# motor_side.net
KiCad netlist of a schematic drawn in EAGLE
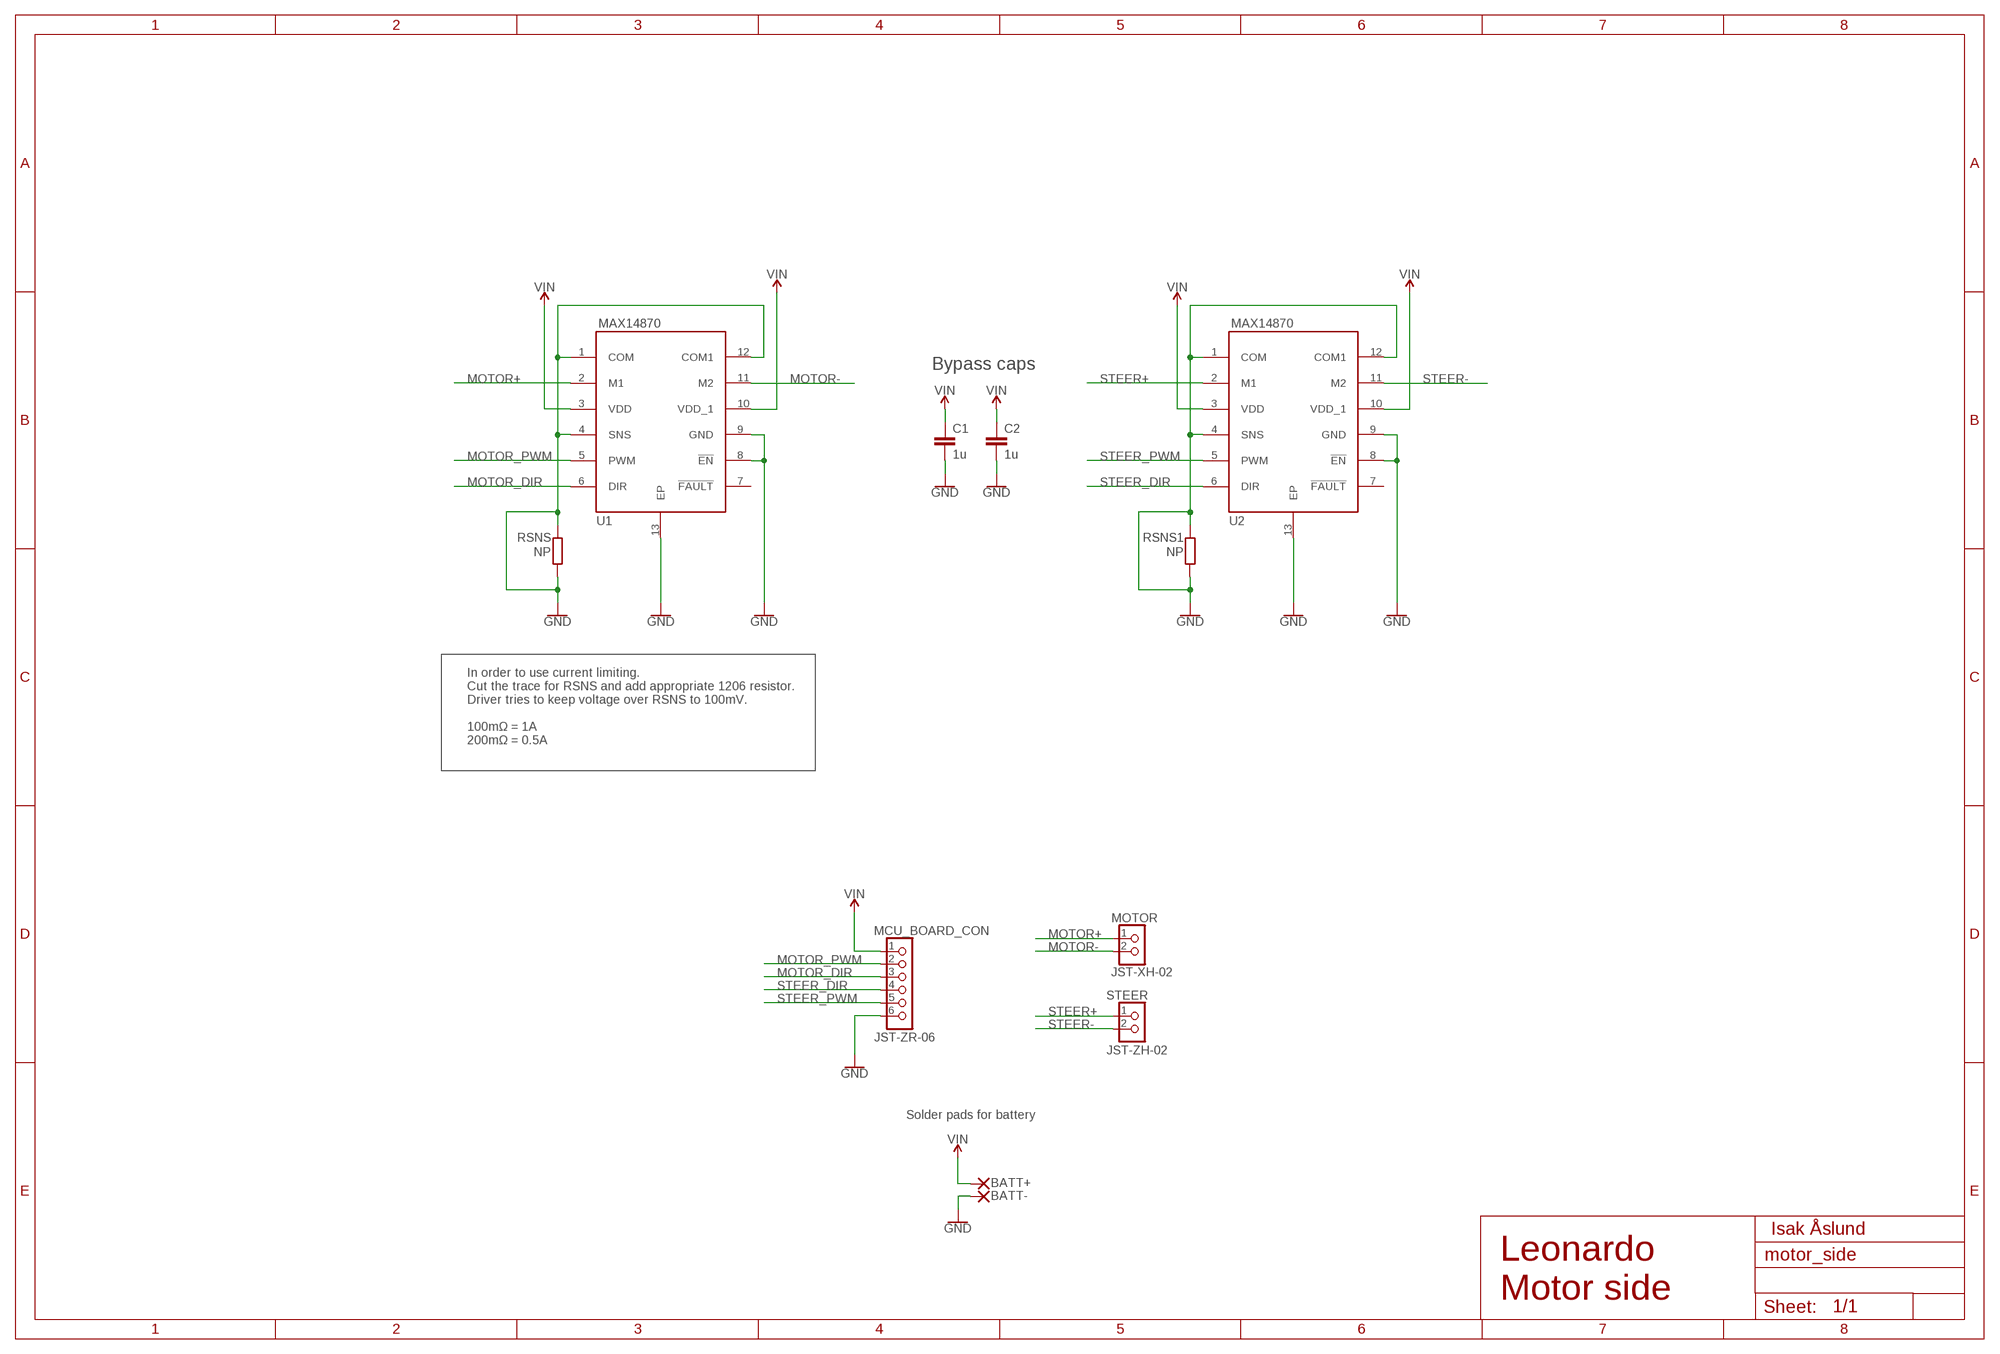
[diagram p0: schematic, sheet 1]

(export (version "E")
  (design (tool "Eeschema 10.0.6"))
  (components
    (comp (ref "BATT+")
      (value "SMD2")
      (footprint "eagle-import:SMD1,27-2,54")
      (libsource (lib "eagle-import") (part "SMD2"))
    )
    (comp (ref "BATT-")
      (value "SMD2")
      (footprint "eagle-import:SMD1,27-2,54")
      (libsource (lib "eagle-import") (part "SMD2"))
    )
    (comp (ref "C1")
      (value "1u")
      (footprint "eagle-import:C0603")
      (libsource (lib "eagle-import") (part "C0603"))
    )
    (comp (ref "C2")
      (value "1u")
      (footprint "eagle-import:C0603")
      (libsource (lib "eagle-import") (part "C0603"))
    )
    (comp (ref "MCU_BOARD_CON")
      (value "JST-ZR-06")
      (footprint "eagle-import:B6B-ZR")
      (libsource (lib "eagle-import") (part "ZR_B6B-ZR"))
    )
    (comp (ref "MOTOR")
      (value "JST-XH-02")
      (footprint "eagle-import:JST-XH-02")
      (libsource (lib "eagle-import") (part "XH-02"))
    )
    (comp (ref "RSNS")
      (value "NP")
      (footprint "eagle-import:R1206")
      (libsource (lib "eagle-import") (part "R1206"))
    )
    (comp (ref "RSNS1")
      (value "NP")
      (footprint "eagle-import:R1206")
      (libsource (lib "eagle-import") (part "R1206"))
    )
    (comp (ref "STEER")
      (value "JST-ZH-02")
      (footprint "eagle-import:B2B-ZR")
      (libsource (lib "eagle-import") (part "ZR_B2B-ZR"))
    )
    (comp (ref "U1")
      (value "MAX14870")
      (footprint "eagle-import:12_TDFN_EP")
      (libsource (lib "eagle-import") (part "MAX14870"))
    )
    (comp (ref "U2")
      (value "MAX14870")
      (footprint "eagle-import:12_TDFN_EP")
      (libsource (lib "eagle-import") (part "MAX14870"))
    )
  )
  (nets
    (net (code "1") (name "/MOTOR+") (class "Default")
      (node (ref "MOTOR") (pin "1") (pinfunction "1_1") (pintype "bidirectional"))
      (node (ref "U1") (pin "2") (pinfunction "M1_2") (pintype "bidirectional"))
    )
    (net (code "2") (name "/MOTOR-") (class "Default")
      (node (ref "MOTOR") (pin "2") (pinfunction "2_2") (pintype "bidirectional"))
      (node (ref "U1") (pin "11") (pinfunction "M2_11") (pintype "bidirectional"))
    )
    (net (code "3") (name "/MOTOR_DIR") (class "Default")
      (node (ref "MCU_BOARD_CON") (pin "3") (pinfunction "3_3") (pintype "passive"))
      (node (ref "U1") (pin "6") (pinfunction "DIR_6") (pintype "bidirectional"))
    )
    (net (code "4") (name "/MOTOR_PWM") (class "Default")
      (node (ref "MCU_BOARD_CON") (pin "2") (pinfunction "2_2") (pintype "passive"))
      (node (ref "U1") (pin "5") (pinfunction "PWM_5") (pintype "bidirectional"))
    )
    (net (code "5") (name "/STEER+") (class "Default")
      (node (ref "STEER") (pin "1") (pinfunction "1_1") (pintype "passive"))
      (node (ref "U2") (pin "2") (pinfunction "M1_2") (pintype "bidirectional"))
    )
    (net (code "6") (name "/STEER-") (class "Default")
      (node (ref "STEER") (pin "2") (pinfunction "2_2") (pintype "passive"))
      (node (ref "U2") (pin "11") (pinfunction "M2_11") (pintype "bidirectional"))
    )
    (net (code "7") (name "/STEER_DIR") (class "Default")
      (node (ref "MCU_BOARD_CON") (pin "4") (pinfunction "4_4") (pintype "passive"))
      (node (ref "U2") (pin "6") (pinfunction "DIR_6") (pintype "bidirectional"))
    )
    (net (code "8") (name "/STEER_PWM") (class "Default")
      (node (ref "MCU_BOARD_CON") (pin "5") (pinfunction "5_5") (pintype "passive"))
      (node (ref "U2") (pin "5") (pinfunction "PWM_5") (pintype "bidirectional"))
    )
    (net (code "9") (name "GND") (class "Default")
      (node (ref "BATT-") (pin "1") (pinfunction "P_1") (pintype "passive"))
      (node (ref "C1") (pin "2") (pinfunction "2_2") (pintype "passive"))
      (node (ref "C2") (pin "2") (pinfunction "2_2") (pintype "passive"))
      (node (ref "MCU_BOARD_CON") (pin "6") (pinfunction "6_6") (pintype "passive"))
      (node (ref "RSNS") (pin "1") (pinfunction "1_1") (pintype "passive"))
      (node (ref "RSNS") (pin "2") (pinfunction "2_2") (pintype "passive"))
      (node (ref "RSNS1") (pin "1") (pinfunction "1_1") (pintype "passive"))
      (node (ref "RSNS1") (pin "2") (pinfunction "2_2") (pintype "passive"))
      (node (ref "U1") (pin "1") (pinfunction "COM_1") (pintype "bidirectional"))
      (node (ref "U1") (pin "12") (pinfunction "COM1_12") (pintype "bidirectional"))
      (node (ref "U1") (pin "13") (pinfunction "EP_13") (pintype "bidirectional"))
      (node (ref "U1") (pin "4") (pinfunction "SNS_4") (pintype "bidirectional"))
      (node (ref "U1") (pin "8") (pinfunction "~{EN}_8") (pintype "bidirectional"))
      (node (ref "U1") (pin "9") (pinfunction "GND_9") (pintype "bidirectional"))
      (node (ref "U2") (pin "1") (pinfunction "COM_1") (pintype "bidirectional"))
      (node (ref "U2") (pin "12") (pinfunction "COM1_12") (pintype "bidirectional"))
      (node (ref "U2") (pin "13") (pinfunction "EP_13") (pintype "bidirectional"))
      (node (ref "U2") (pin "4") (pinfunction "SNS_4") (pintype "bidirectional"))
      (node (ref "U2") (pin "8") (pinfunction "~{EN}_8") (pintype "bidirectional"))
      (node (ref "U2") (pin "9") (pinfunction "GND_9") (pintype "bidirectional"))
    )
    (net (code "10") (name "VIN") (class "Default")
      (node (ref "BATT+") (pin "1") (pinfunction "P_1") (pintype "passive"))
      (node (ref "C1") (pin "1") (pinfunction "1_1") (pintype "passive"))
      (node (ref "C2") (pin "1") (pinfunction "1_1") (pintype "passive"))
      (node (ref "MCU_BOARD_CON") (pin "1") (pinfunction "1_1") (pintype "passive"))
      (node (ref "U1") (pin "10") (pinfunction "VDD_1_10") (pintype "bidirectional"))
      (node (ref "U1") (pin "3") (pinfunction "VDD_3") (pintype "bidirectional"))
      (node (ref "U2") (pin "10") (pinfunction "VDD_1_10") (pintype "bidirectional"))
      (node (ref "U2") (pin "3") (pinfunction "VDD_3") (pintype "bidirectional"))
    )
    (net (code "11") (name "unconnected-(U1-~{FAULT}-Pad7)") (class "Default")
      (node (ref "U1") (pin "7") (pinfunction "~{FAULT}_7") (pintype "bidirectional"))
    )
    (net (code "12") (name "unconnected-(U2-~{FAULT}-Pad7)") (class "Default")
      (node (ref "U2") (pin "7") (pinfunction "~{FAULT}_7") (pintype "bidirectional"))
    )
  )
)
